# HiSpeedADC.net
KiCad netlist of a schematic drawn in Altium Designer
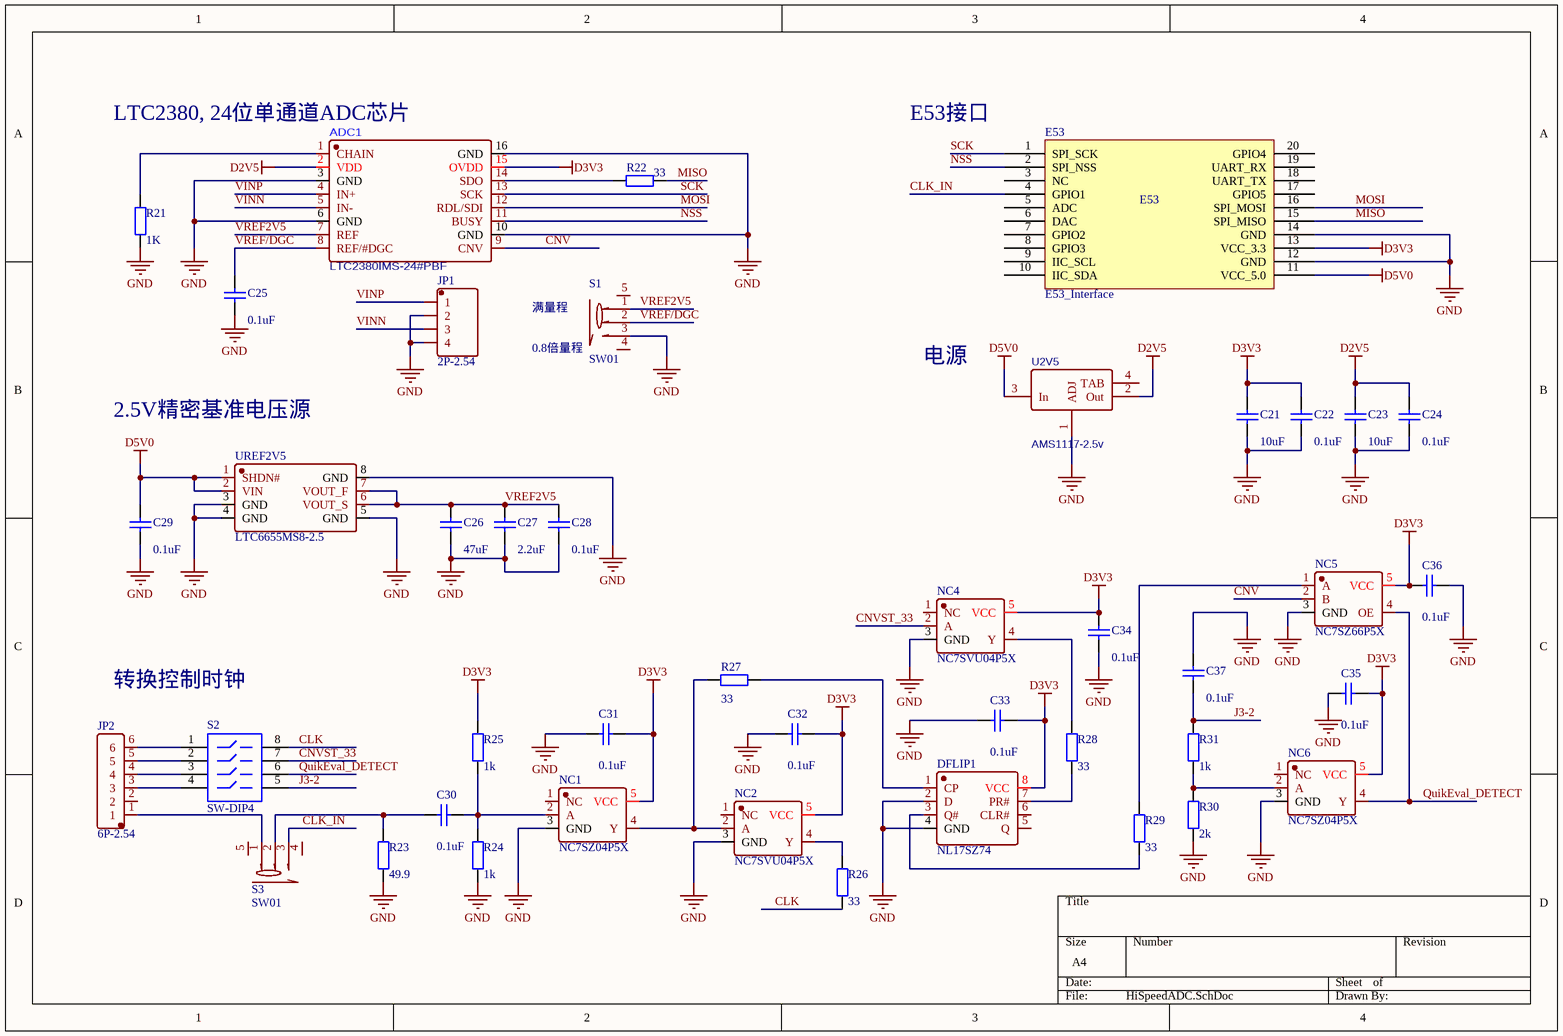
[diagram p0: HiSpeedADC.SchDoc]

(export (version "E")
  (design (tool "Eeschema 10.0.6"))
  (components
    (comp (ref "ADC1") (value "LTC2380IMS-24#PBF") (libsource (lib "NBIoT") (part "LTC2380IMS-24#PBF")))
    (comp (ref "C21")
      (value "10uF")
      (footprint "C1206")
      (description "Capacitor (Semiconductor SIM Model)")
      (fields (field (name "PUBLISHER") "Altium Limited"))
      (libsource (lib "Miscellaneous Devices") (part "Cap Semi"))
    )
    (comp (ref "C22")
      (value "0.1uF")
      (footprint "C1206")
      (description "Capacitor (Semiconductor SIM Model)")
      (fields (field (name "PUBLISHER") "Altium Limited"))
      (libsource (lib "Miscellaneous Devices") (part "Cap Semi"))
    )
    (comp (ref "C23")
      (value "10uF")
      (footprint "C1206")
      (description "Capacitor (Semiconductor SIM Model)")
      (fields (field (name "PUBLISHER") "Altium Limited"))
      (libsource (lib "Miscellaneous Devices") (part "Cap Semi"))
    )
    (comp (ref "C24")
      (value "0.1uF")
      (footprint "C1206")
      (description "Capacitor (Semiconductor SIM Model)")
      (fields (field (name "PUBLISHER") "Altium Limited"))
      (libsource (lib "Miscellaneous Devices") (part "Cap Semi"))
    )
    (comp (ref "C25")
      (value "0.1uF")
      (footprint "C1206")
      (description "Capacitor (Semiconductor SIM Model)")
      (fields (field (name "PUBLISHER") "Altium Limited"))
      (libsource (lib "Miscellaneous Devices") (part "Cap Semi"))
    )
    (comp (ref "C26")
      (value "47uF")
      (footprint "C1206")
      (description "Capacitor (Semiconductor SIM Model)")
      (fields (field (name "PUBLISHER") "Altium Limited"))
      (libsource (lib "Miscellaneous Devices") (part "Cap Semi"))
    )
    (comp (ref "C27")
      (value "2.2uF")
      (footprint "C1206")
      (description "Capacitor (Semiconductor SIM Model)")
      (fields (field (name "PUBLISHER") "Altium Limited"))
      (libsource (lib "Miscellaneous Devices") (part "Cap Semi"))
    )
    (comp (ref "C28")
      (value "0.1uF")
      (footprint "C1206")
      (description "Capacitor (Semiconductor SIM Model)")
      (fields (field (name "PUBLISHER") "Altium Limited"))
      (libsource (lib "Miscellaneous Devices") (part "Cap Semi"))
    )
    (comp (ref "C29")
      (value "0.1uF")
      (footprint "C1206")
      (description "Capacitor (Semiconductor SIM Model)")
      (fields (field (name "PUBLISHER") "Altium Limited"))
      (libsource (lib "Miscellaneous Devices") (part "Cap Semi"))
    )
    (comp (ref "C30")
      (value "0.1uF")
      (footprint "C1206")
      (description "Capacitor (Semiconductor SIM Model)")
      (fields (field (name "PUBLISHER") "Altium Limited"))
      (libsource (lib "Miscellaneous Devices") (part "Cap Semi"))
    )
    (comp (ref "C31")
      (value "0.1uF")
      (footprint "C1206")
      (description "Capacitor (Semiconductor SIM Model)")
      (fields (field (name "PUBLISHER") "Altium Limited"))
      (libsource (lib "Miscellaneous Devices") (part "Cap Semi"))
    )
    (comp (ref "C32")
      (value "0.1uF")
      (footprint "C1206")
      (description "Capacitor (Semiconductor SIM Model)")
      (fields (field (name "PUBLISHER") "Altium Limited"))
      (libsource (lib "Miscellaneous Devices") (part "Cap Semi"))
    )
    (comp (ref "C33")
      (value "0.1uF")
      (footprint "C1206")
      (description "Capacitor (Semiconductor SIM Model)")
      (fields (field (name "PUBLISHER") "Altium Limited"))
      (libsource (lib "Miscellaneous Devices") (part "Cap Semi"))
    )
    (comp (ref "C34")
      (value "0.1uF")
      (footprint "C1206")
      (description "Capacitor (Semiconductor SIM Model)")
      (fields (field (name "PUBLISHER") "Altium Limited"))
      (libsource (lib "Miscellaneous Devices") (part "Cap Semi"))
    )
    (comp (ref "C35")
      (value "0.1uF")
      (footprint "C1206")
      (description "Capacitor (Semiconductor SIM Model)")
      (fields (field (name "PUBLISHER") "Altium Limited"))
      (libsource (lib "Miscellaneous Devices") (part "Cap Semi"))
    )
    (comp (ref "C36")
      (value "0.1uF")
      (footprint "C1206")
      (description "Capacitor (Semiconductor SIM Model)")
      (fields (field (name "PUBLISHER") "Altium Limited"))
      (libsource (lib "Miscellaneous Devices") (part "Cap Semi"))
    )
    (comp (ref "C37")
      (value "0.1uF")
      (footprint "C1206")
      (description "Capacitor (Semiconductor SIM Model)")
      (fields (field (name "PUBLISHER") "Altium Limited"))
      (libsource (lib "Miscellaneous Devices") (part "Cap Semi"))
    )
    (comp (ref "DFLIP1")
      (value "NL17SZ74")
      (footprint "US-8_L2.4-W2.1-P0.50-LS3.2-BR")
      (libsource (lib "NBIoT") (part "NL17SZ74"))
    )
    (comp (ref "E53")
      (value "E53_Interface")
      (footprint "EXT_M_BearPi")
      (libsource (lib "BearPi_RevB01") (part "E53"))
    )
    (comp (ref "JP1")
      (value "2P-2.54")
      (footprint "HDR-TH_4P-P2.54-V")
      (libsource (lib "NBIoT") (part "2P-2.54"))
    )
    (comp (ref "JP2")
      (value "6P-2.54")
      (footprint "HDR-TH_6P-P2.54-V")
      (libsource (lib "NBIoT") (part "6P-2.54"))
    )
    (comp (ref "NC1")
      (value "NC7SZ04P5X")
      (footprint "SC-70-5_L2.1-W1.3-P0.65-LS2.1-BR")
      (libsource (lib "NBIoT") (part "NC7SZ04P5X"))
    )
    (comp (ref "NC2")
      (value "NC7SVU04P5X")
      (footprint "SC-70-5_L2.1-W1.3-P0.65-LS2.1-BL")
      (libsource (lib "NBIoT") (part "NC7SVU04P5X"))
    )
    (comp (ref "NC4")
      (value "NC7SVU04P5X")
      (footprint "SC-70-5_L2.1-W1.3-P0.65-LS2.1-BL")
      (libsource (lib "NBIoT") (part "NC7SVU04P5X"))
    )
    (comp (ref "NC5")
      (value "NC7SZ66P5X")
      (footprint "SC-70-5_L2.1-W1.3-P0.65-LS2.1-BL")
      (libsource (lib "NBIoT") (part "NC7SZ66P5X"))
    )
    (comp (ref "NC6")
      (value "NC7SZ04P5X")
      (footprint "SC-70-5_L2.1-W1.3-P0.65-LS2.1-BR")
      (libsource (lib "NBIoT") (part "NC7SZ04P5X"))
    )
    (comp (ref "R21")
      (value "1K")
      (footprint "6-0805_N")
      (description "Resistor")
      (fields (field (name "PUBLISHER") "Altium Limited"))
      (libsource (lib "") (part "Res2_2"))
    )
    (comp (ref "R22")
      (value "33")
      (footprint "6-0805_N")
      (description "Resistor")
      (fields (field (name "PUBLISHER") "Altium Limited"))
      (libsource (lib "") (part "Res2_1"))
    )
    (comp (ref "R23")
      (value "49.9")
      (footprint "6-0805_N")
      (description "Resistor")
      (fields (field (name "PUBLISHER") "Altium Limited"))
      (libsource (lib "Miscellaneous Devices") (part "Res2"))
    )
    (comp (ref "R24")
      (value "1k")
      (footprint "6-0805_N")
      (description "Resistor")
      (fields (field (name "PUBLISHER") "Altium Limited"))
      (libsource (lib "Miscellaneous Devices") (part "Res2"))
    )
    (comp (ref "R25")
      (value "1k")
      (footprint "6-0805_N")
      (description "Resistor")
      (fields (field (name "PUBLISHER") "Altium Limited"))
      (libsource (lib "Miscellaneous Devices") (part "Res2"))
    )
    (comp (ref "R26")
      (value "33")
      (footprint "6-0805_N")
      (description "Resistor")
      (fields (field (name "PUBLISHER") "Altium Limited"))
      (libsource (lib "") (part "Res2_2"))
    )
    (comp (ref "R27")
      (value "33")
      (footprint "6-0805_N")
      (description "Resistor")
      (fields (field (name "PUBLISHER") "Altium Limited"))
      (libsource (lib "") (part "Res2_1"))
    )
    (comp (ref "R28")
      (value "33")
      (footprint "6-0805_N")
      (description "Resistor")
      (fields (field (name "PUBLISHER") "Altium Limited"))
      (libsource (lib "Miscellaneous Devices") (part "Res2"))
    )
    (comp (ref "R29")
      (value "33")
      (footprint "6-0805_N")
      (description "Resistor")
      (fields (field (name "PUBLISHER") "Altium Limited"))
      (libsource (lib "") (part "Res2_2"))
    )
    (comp (ref "R30")
      (value "2k")
      (footprint "6-0805_N")
      (description "Resistor")
      (fields (field (name "PUBLISHER") "Altium Limited"))
      (libsource (lib "") (part "Res2_2"))
    )
    (comp (ref "R31")
      (value "1k")
      (footprint "6-0805_N")
      (description "Resistor")
      (fields (field (name "PUBLISHER") "Altium Limited"))
      (libsource (lib "") (part "Res2_2"))
    )
    (comp (ref "S1") (value "SW01") (footprint "SW-TH_SSSU011700") (libsource (lib "NBIoT") (part "SW01")))
    (comp (ref "S2")
      (value "SW-DIP4")
      (footprint "DIP-8")
      (description "DIP Switch")
      (fields (field (name "PUBLISHER") "Altium Limited"))
      (libsource (lib "Miscellaneous Devices") (part "SW-DIP4"))
    )
    (comp (ref "S3") (value "SW01") (footprint "SW-TH_SSSU011700") (libsource (lib "NBIoT") (part "SW01")))
    (comp (ref "U2V5")
      (value "AMS1117-2.5v")
      (footprint "SOT-223_L6.7-W3.5-P2.30-BR")
      (fields
        (field (name "BOM_MANUFACTURER PART") "AMS1117-ADJ")
        (field (name "BOM_SUPPLIER PART") "C6188")
        (field (name "CONTRIBUTOR") "GerryChen")
      )
      (libsource (lib "NBIoT") (part "AMS1117-ADJ"))
    )
    (comp (ref "UREF2V5") (value "LTC6655MS8-2.5") (libsource (lib "NBIoT") (part "LTC6655MS8-5")))
  )
  (nets
    (net (code "1") (name "/CLK") (class "Default")
      (node (ref "R26") (pin "1") (pinfunction "1_1") (pintype "passive"))
      (node (ref "S2") (pin "8") (pinfunction "8_8") (pintype "passive"))
    )
    (net (code "2") (name "/CLK_IN") (class "Default")
      (node (ref "E53") (pin "4") (pinfunction "GPIO1_4") (pintype "passive"))
      (node (ref "S3") (pin "3") (pinfunction "3_3") (pintype "passive"))
    )
    (net (code "3") (name "/CNV") (class "Default")
      (node (ref "ADC1") (pin "9") (pinfunction "CNV_9") (pintype "passive"))
      (node (ref "NC5") (pin "2") (pinfunction "B_2") (pintype "passive"))
    )
    (net (code "4") (name "/CNVST_33") (class "Default")
      (node (ref "NC4") (pin "2") (pinfunction "A_2") (pintype "passive"))
      (node (ref "S2") (pin "7") (pinfunction "7_7") (pintype "passive"))
    )
    (net (code "5") (name "/J3-2") (class "Default")
      (node (ref "C37") (pin "1") (pinfunction "1_1") (pintype "passive"))
      (node (ref "R31") (pin "2") (pinfunction "2_2") (pintype "passive"))
      (node (ref "S2") (pin "5") (pinfunction "5_5") (pintype "passive"))
    )
    (net (code "6") (name "/MISO") (class "Default")
      (node (ref "E53") (pin "15") (pinfunction "SPI_MISO_15") (pintype "passive"))
      (node (ref "R22") (pin "1") (pinfunction "1_1") (pintype "passive"))
    )
    (net (code "7") (name "/MOSI") (class "Default")
      (node (ref "ADC1") (pin "12") (pinfunction "RDL/SDI_12") (pintype "passive"))
      (node (ref "E53") (pin "16") (pinfunction "SPI_MOSI_16") (pintype "passive"))
    )
    (net (code "8") (name "/NSS") (class "Default")
      (node (ref "ADC1") (pin "11") (pinfunction "BUSY_11") (pintype "passive"))
      (node (ref "E53") (pin "2") (pinfunction "SPI_NSS_2") (pintype "passive"))
    )
    (net (code "9") (name "/QuikEval_DETECT") (class "Default")
      (node (ref "NC5") (pin "4") (pinfunction "OE_4") (pintype "passive"))
      (node (ref "NC6") (pin "4") (pinfunction "Y_4") (pintype "passive"))
      (node (ref "S2") (pin "6") (pinfunction "6_6") (pintype "passive"))
    )
    (net (code "10") (name "/SCK") (class "Default")
      (node (ref "ADC1") (pin "13") (pinfunction "SCK_13") (pintype "passive"))
      (node (ref "E53") (pin "1") (pinfunction "SPI_SCK_1") (pintype "passive"))
    )
    (net (code "11") (name "/VINN") (class "Default")
      (node (ref "ADC1") (pin "5") (pinfunction "IN-_5") (pintype "passive"))
      (node (ref "JP1") (pin "3") (pinfunction "3_3") (pintype "passive"))
    )
    (net (code "12") (name "/VINP") (class "Default")
      (node (ref "ADC1") (pin "4") (pinfunction "IN+_4") (pintype "passive"))
      (node (ref "JP1") (pin "1") (pinfunction "1_1") (pintype "passive"))
    )
    (net (code "13") (name "/VREF2V5") (class "Default")
      (node (ref "ADC1") (pin "7") (pinfunction "REF_7") (pintype "passive"))
      (node (ref "C26") (pin "1") (pinfunction "1_1") (pintype "passive"))
      (node (ref "C27") (pin "1") (pinfunction "1_1") (pintype "passive"))
      (node (ref "C28") (pin "1") (pinfunction "1_1") (pintype "passive"))
      (node (ref "S1") (pin "1") (pinfunction "1_1") (pintype "passive"))
      (node (ref "UREF2V5") (pin "6") (pinfunction "VOUT_S_6") (pintype "passive"))
      (node (ref "UREF2V5") (pin "7") (pinfunction "VOUT_F_7") (pintype "passive"))
    )
    (net (code "14") (name "/VREF{slash}DGC") (class "Default")
      (node (ref "ADC1") (pin "8") (pinfunction "REF/#DGC_8") (pintype "passive"))
      (node (ref "C25") (pin "1") (pinfunction "1_1") (pintype "passive"))
      (node (ref "S1") (pin "2") (pinfunction "2_2") (pintype "passive"))
    )
    (net (code "15") (name "D2V5") (class "Default")
      (node (ref "ADC1") (pin "2") (pinfunction "VDD_2") (pintype "passive"))
      (node (ref "C23") (pin "1") (pinfunction "1_1") (pintype "passive"))
      (node (ref "C24") (pin "1") (pinfunction "1_1") (pintype "passive"))
      (node (ref "U2V5") (pin "2") (pinfunction "Out_2") (pintype "passive"))
    )
    (net (code "16") (name "D3V3") (class "Default")
      (node (ref "ADC1") (pin "15") (pinfunction "OVDD_15") (pintype "passive"))
      (node (ref "C21") (pin "1") (pinfunction "1_1") (pintype "passive"))
      (node (ref "C22") (pin "1") (pinfunction "1_1") (pintype "passive"))
      (node (ref "C31") (pin "2") (pinfunction "2_2") (pintype "passive"))
      (node (ref "C32") (pin "2") (pinfunction "2_2") (pintype "passive"))
      (node (ref "C33") (pin "1") (pinfunction "1_1") (pintype "passive"))
      (node (ref "C34") (pin "1") (pinfunction "1_1") (pintype "passive"))
      (node (ref "C35") (pin "2") (pinfunction "2_2") (pintype "passive"))
      (node (ref "C36") (pin "1") (pinfunction "1_1") (pintype "passive"))
      (node (ref "DFLIP1") (pin "8") (pinfunction "VCC_8") (pintype "passive"))
      (node (ref "E53") (pin "13") (pinfunction "VCC_3.3_13") (pintype "passive"))
      (node (ref "NC1") (pin "5") (pinfunction "VCC_5") (pintype "passive"))
      (node (ref "NC2") (pin "5") (pinfunction "VCC_5") (pintype "passive"))
      (node (ref "NC4") (pin "5") (pinfunction "VCC_5") (pintype "passive"))
      (node (ref "NC5") (pin "5") (pinfunction "VCC_5") (pintype "passive"))
      (node (ref "NC6") (pin "5") (pinfunction "VCC_5") (pintype "passive"))
      (node (ref "R25") (pin "1") (pinfunction "1_1") (pintype "passive"))
    )
    (net (code "17") (name "D5V0") (class "Default")
      (node (ref "C29") (pin "1") (pinfunction "1_1") (pintype "passive"))
      (node (ref "E53") (pin "11") (pinfunction "VCC_5.0_11") (pintype "passive"))
      (node (ref "U2V5") (pin "3") (pinfunction "In_3") (pintype "passive"))
      (node (ref "UREF2V5") (pin "1") (pinfunction "SHDN#_1") (pintype "passive"))
      (node (ref "UREF2V5") (pin "2") (pinfunction "VIN_2") (pintype "passive"))
    )
    (net (code "18") (name "GND") (class "Default")
      (node (ref "ADC1") (pin "10") (pinfunction "GND_10") (pintype "passive"))
      (node (ref "ADC1") (pin "16") (pinfunction "GND_16") (pintype "passive"))
      (node (ref "ADC1") (pin "3") (pinfunction "GND_3") (pintype "passive"))
      (node (ref "ADC1") (pin "6") (pinfunction "GND_6") (pintype "passive"))
      (node (ref "C21") (pin "2") (pinfunction "2_2") (pintype "passive"))
      (node (ref "C22") (pin "2") (pinfunction "2_2") (pintype "passive"))
      (node (ref "C23") (pin "2") (pinfunction "2_2") (pintype "passive"))
      (node (ref "C24") (pin "2") (pinfunction "2_2") (pintype "passive"))
      (node (ref "C25") (pin "2") (pinfunction "2_2") (pintype "passive"))
      (node (ref "C26") (pin "2") (pinfunction "2_2") (pintype "passive"))
      (node (ref "C27") (pin "2") (pinfunction "2_2") (pintype "passive"))
      (node (ref "C28") (pin "2") (pinfunction "2_2") (pintype "passive"))
      (node (ref "C29") (pin "2") (pinfunction "2_2") (pintype "passive"))
      (node (ref "C31") (pin "1") (pinfunction "1_1") (pintype "passive"))
      (node (ref "C32") (pin "1") (pinfunction "1_1") (pintype "passive"))
      (node (ref "C33") (pin "2") (pinfunction "2_2") (pintype "passive"))
      (node (ref "C34") (pin "2") (pinfunction "2_2") (pintype "passive"))
      (node (ref "C35") (pin "1") (pinfunction "1_1") (pintype "passive"))
      (node (ref "C36") (pin "2") (pinfunction "2_2") (pintype "passive"))
      (node (ref "C37") (pin "2") (pinfunction "2_2") (pintype "passive"))
      (node (ref "DFLIP1") (pin "2") (pinfunction "D_2") (pintype "passive"))
      (node (ref "DFLIP1") (pin "4") (pinfunction "GND_4") (pintype "passive"))
      (node (ref "E53") (pin "12") (pinfunction "GND_12") (pintype "passive"))
      (node (ref "E53") (pin "14") (pinfunction "GND_14") (pintype "passive"))
      (node (ref "JP1") (pin "2") (pinfunction "2_2") (pintype "passive"))
      (node (ref "JP1") (pin "4") (pinfunction "4_4") (pintype "passive"))
      (node (ref "NC1") (pin "3") (pinfunction "GND_3") (pintype "passive"))
      (node (ref "NC2") (pin "3") (pinfunction "GND_3") (pintype "passive"))
      (node (ref "NC4") (pin "3") (pinfunction "GND_3") (pintype "passive"))
      (node (ref "NC5") (pin "3") (pinfunction "GND_3") (pintype "passive"))
      (node (ref "NC6") (pin "3") (pinfunction "GND_3") (pintype "passive"))
      (node (ref "R21") (pin "1") (pinfunction "1_1") (pintype "passive"))
      (node (ref "R23") (pin "2") (pinfunction "2_2") (pintype "passive"))
      (node (ref "R24") (pin "2") (pinfunction "2_2") (pintype "passive"))
      (node (ref "R30") (pin "1") (pinfunction "1_1") (pintype "passive"))
      (node (ref "S1") (pin "3") (pinfunction "3_3") (pintype "passive"))
      (node (ref "U2V5") (pin "1") (pinfunction "ADJ_1") (pintype "passive"))
      (node (ref "UREF2V5") (pin "3") (pinfunction "GND_3") (pintype "passive"))
      (node (ref "UREF2V5") (pin "4") (pinfunction "GND_4") (pintype "passive"))
      (node (ref "UREF2V5") (pin "5") (pinfunction "GND_5") (pintype "passive"))
      (node (ref "UREF2V5") (pin "8") (pinfunction "GND_8") (pintype "passive"))
    )
    (net (code "19") (name "Net-(ADC1-CHAIN)") (class "Default")
      (node (ref "ADC1") (pin "1") (pinfunction "CHAIN_1") (pintype "passive"))
      (node (ref "R21") (pin "2") (pinfunction "2_2") (pintype "passive"))
    )
    (net (code "20") (name "Net-(ADC1-SDO)") (class "Default")
      (node (ref "ADC1") (pin "14") (pinfunction "SDO_14") (pintype "passive"))
      (node (ref "R22") (pin "2") (pinfunction "2_2") (pintype "passive"))
    )
    (net (code "21") (name "Net-(C30-Pad1)") (class "Default")
      (node (ref "C30") (pin "1") (pinfunction "1_1") (pintype "passive"))
      (node (ref "R23") (pin "1") (pinfunction "1_1") (pintype "passive"))
      (node (ref "S3") (pin "2") (pinfunction "2_2") (pintype "passive"))
    )
    (net (code "22") (name "Net-(DFLIP1-CP)") (class "Default")
      (node (ref "DFLIP1") (pin "1") (pinfunction "CP_1") (pintype "passive"))
      (node (ref "R27") (pin "1") (pinfunction "1_1") (pintype "passive"))
    )
    (net (code "23") (name "Net-(DFLIP1-PR#)") (class "Default")
      (node (ref "DFLIP1") (pin "7") (pinfunction "PR#_7") (pintype "passive"))
      (node (ref "R28") (pin "2") (pinfunction "2_2") (pintype "passive"))
    )
    (net (code "24") (name "Net-(DFLIP1-Q#)") (class "Default")
      (node (ref "DFLIP1") (pin "3") (pinfunction "Q#_3") (pintype "passive"))
      (node (ref "R29") (pin "1") (pinfunction "1_1") (pintype "passive"))
    )
    (net (code "25") (name "Net-(JP2-Pad1)") (class "Default")
      (node (ref "JP2") (pin "1") (pinfunction "1_1") (pintype "passive"))
      (node (ref "S3") (pin "1") (pinfunction "1_1") (pintype "passive"))
    )
    (net (code "26") (name "Net-(JP2-Pad3)") (class "Default")
      (node (ref "JP2") (pin "3") (pinfunction "3_3") (pintype "passive"))
      (node (ref "S2") (pin "4") (pinfunction "4_4") (pintype "passive"))
    )
    (net (code "27") (name "Net-(JP2-Pad4)") (class "Default")
      (node (ref "JP2") (pin "4") (pinfunction "4_4") (pintype "passive"))
      (node (ref "S2") (pin "3") (pinfunction "3_3") (pintype "passive"))
    )
    (net (code "28") (name "Net-(JP2-Pad5)") (class "Default")
      (node (ref "JP2") (pin "5") (pinfunction "5_5") (pintype "passive"))
      (node (ref "S2") (pin "2") (pinfunction "2_2") (pintype "passive"))
    )
    (net (code "29") (name "Net-(JP2-Pad6)") (class "Default")
      (node (ref "JP2") (pin "6") (pinfunction "6_6") (pintype "passive"))
      (node (ref "S2") (pin "1") (pinfunction "1_1") (pintype "passive"))
    )
    (net (code "30") (name "Net-(NC1-A)") (class "Default")
      (node (ref "C30") (pin "2") (pinfunction "2_2") (pintype "passive"))
      (node (ref "NC1") (pin "2") (pinfunction "A_2") (pintype "passive"))
      (node (ref "R24") (pin "1") (pinfunction "1_1") (pintype "passive"))
      (node (ref "R25") (pin "2") (pinfunction "2_2") (pintype "passive"))
    )
    (net (code "31") (name "Net-(NC1-Y)") (class "Default")
      (node (ref "NC1") (pin "4") (pinfunction "Y_4") (pintype "passive"))
      (node (ref "NC2") (pin "2") (pinfunction "A_2") (pintype "passive"))
      (node (ref "R27") (pin "2") (pinfunction "2_2") (pintype "passive"))
    )
    (net (code "32") (name "Net-(NC2-Y)") (class "Default")
      (node (ref "NC2") (pin "4") (pinfunction "Y_4") (pintype "passive"))
      (node (ref "R26") (pin "2") (pinfunction "2_2") (pintype "passive"))
    )
    (net (code "33") (name "Net-(NC4-Y)") (class "Default")
      (node (ref "NC4") (pin "4") (pinfunction "Y_4") (pintype "passive"))
      (node (ref "R28") (pin "1") (pinfunction "1_1") (pintype "passive"))
    )
    (net (code "34") (name "Net-(NC5-A)") (class "Default")
      (node (ref "NC5") (pin "1") (pinfunction "A_1") (pintype "passive"))
      (node (ref "R29") (pin "2") (pinfunction "2_2") (pintype "passive"))
    )
    (net (code "35") (name "Net-(NC6-A)") (class "Default")
      (node (ref "NC6") (pin "2") (pinfunction "A_2") (pintype "passive"))
      (node (ref "R30") (pin "2") (pinfunction "2_2") (pintype "passive"))
      (node (ref "R31") (pin "1") (pinfunction "1_1") (pintype "passive"))
    )
    (net (code "36") (name "unconnected-(DFLIP1-CLR#-Pad6)") (class "Default")
      (node (ref "DFLIP1") (pin "6") (pinfunction "CLR#_6") (pintype "passive"))
    )
    (net (code "37") (name "unconnected-(DFLIP1-Q-Pad5)") (class "Default")
      (node (ref "DFLIP1") (pin "5") (pinfunction "Q_5") (pintype "passive"))
    )
    (net (code "38") (name "unconnected-(E53-ADC-Pad5)") (class "Default")
      (node (ref "E53") (pin "5") (pinfunction "ADC_5") (pintype "passive"))
    )
    (net (code "39") (name "unconnected-(E53-DAC-Pad6)") (class "Default")
      (node (ref "E53") (pin "6") (pinfunction "DAC_6") (pintype "passive"))
    )
    (net (code "40") (name "unconnected-(E53-GPIO2-Pad7)") (class "Default")
      (node (ref "E53") (pin "7") (pinfunction "GPIO2_7") (pintype "passive"))
    )
    (net (code "41") (name "unconnected-(E53-GPIO3-Pad8)") (class "Default")
      (node (ref "E53") (pin "8") (pinfunction "GPIO3_8") (pintype "passive"))
    )
    (net (code "42") (name "unconnected-(E53-GPIO4-Pad20)") (class "Default")
      (node (ref "E53") (pin "20") (pinfunction "GPIO4_20") (pintype "passive"))
    )
    (net (code "43") (name "unconnected-(E53-GPIO5-Pad17)") (class "Default")
      (node (ref "E53") (pin "17") (pinfunction "GPIO5_17") (pintype "passive"))
    )
    (net (code "44") (name "unconnected-(E53-IIC_SCL-Pad9)") (class "Default")
      (node (ref "E53") (pin "9") (pinfunction "IIC_SCL_9") (pintype "passive"))
    )
    (net (code "45") (name "unconnected-(E53-IIC_SDA-Pad10)") (class "Default")
      (node (ref "E53") (pin "10") (pinfunction "IIC_SDA_10") (pintype "passive"))
    )
    (net (code "46") (name "unconnected-(E53-NC-Pad3)") (class "Default")
      (node (ref "E53") (pin "3") (pinfunction "NC_3") (pintype "passive"))
    )
    (net (code "47") (name "unconnected-(E53-UART_RX-Pad19)") (class "Default")
      (node (ref "E53") (pin "19") (pinfunction "UART_RX_19") (pintype "passive"))
    )
    (net (code "48") (name "unconnected-(E53-UART_TX-Pad18)") (class "Default")
      (node (ref "E53") (pin "18") (pinfunction "UART_TX_18") (pintype "passive"))
    )
    (net (code "49") (name "unconnected-(JP2-Pad2)") (class "Default")
      (node (ref "JP2") (pin "2") (pinfunction "2_2") (pintype "passive"))
    )
    (net (code "50") (name "unconnected-(NC1-NC-Pad1)") (class "Default")
      (node (ref "NC1") (pin "1") (pinfunction "NC_1") (pintype "passive"))
    )
    (net (code "51") (name "unconnected-(NC2-NC-Pad1)") (class "Default")
      (node (ref "NC2") (pin "1") (pinfunction "NC_1") (pintype "passive"))
    )
    (net (code "52") (name "unconnected-(NC4-NC-Pad1)") (class "Default")
      (node (ref "NC4") (pin "1") (pinfunction "NC_1") (pintype "passive"))
    )
    (net (code "53") (name "unconnected-(NC6-NC-Pad1)") (class "Default")
      (node (ref "NC6") (pin "1") (pinfunction "NC_1") (pintype "passive"))
    )
    (net (code "54") (name "unconnected-(S1-Pad4)") (class "Default")
      (node (ref "S1") (pin "4") (pinfunction "4_4") (pintype "passive"))
    )
    (net (code "55") (name "unconnected-(S1-Pad5)") (class "Default")
      (node (ref "S1") (pin "5") (pinfunction "5_5") (pintype "passive"))
    )
    (net (code "56") (name "unconnected-(S3-Pad4)") (class "Default")
      (node (ref "S3") (pin "4") (pinfunction "4_4") (pintype "passive"))
    )
    (net (code "57") (name "unconnected-(S3-Pad5)") (class "Default")
      (node (ref "S3") (pin "5") (pinfunction "5_5") (pintype "passive"))
    )
    (net (code "58") (name "unconnected-(U2V5-TAB-Pad4)") (class "Default")
      (node (ref "U2V5") (pin "4") (pinfunction "TAB_4") (pintype "passive"))
    )
  )
)
